# Sensor_Board.net
KiCad netlist of a schematic drawn in Altium Designer
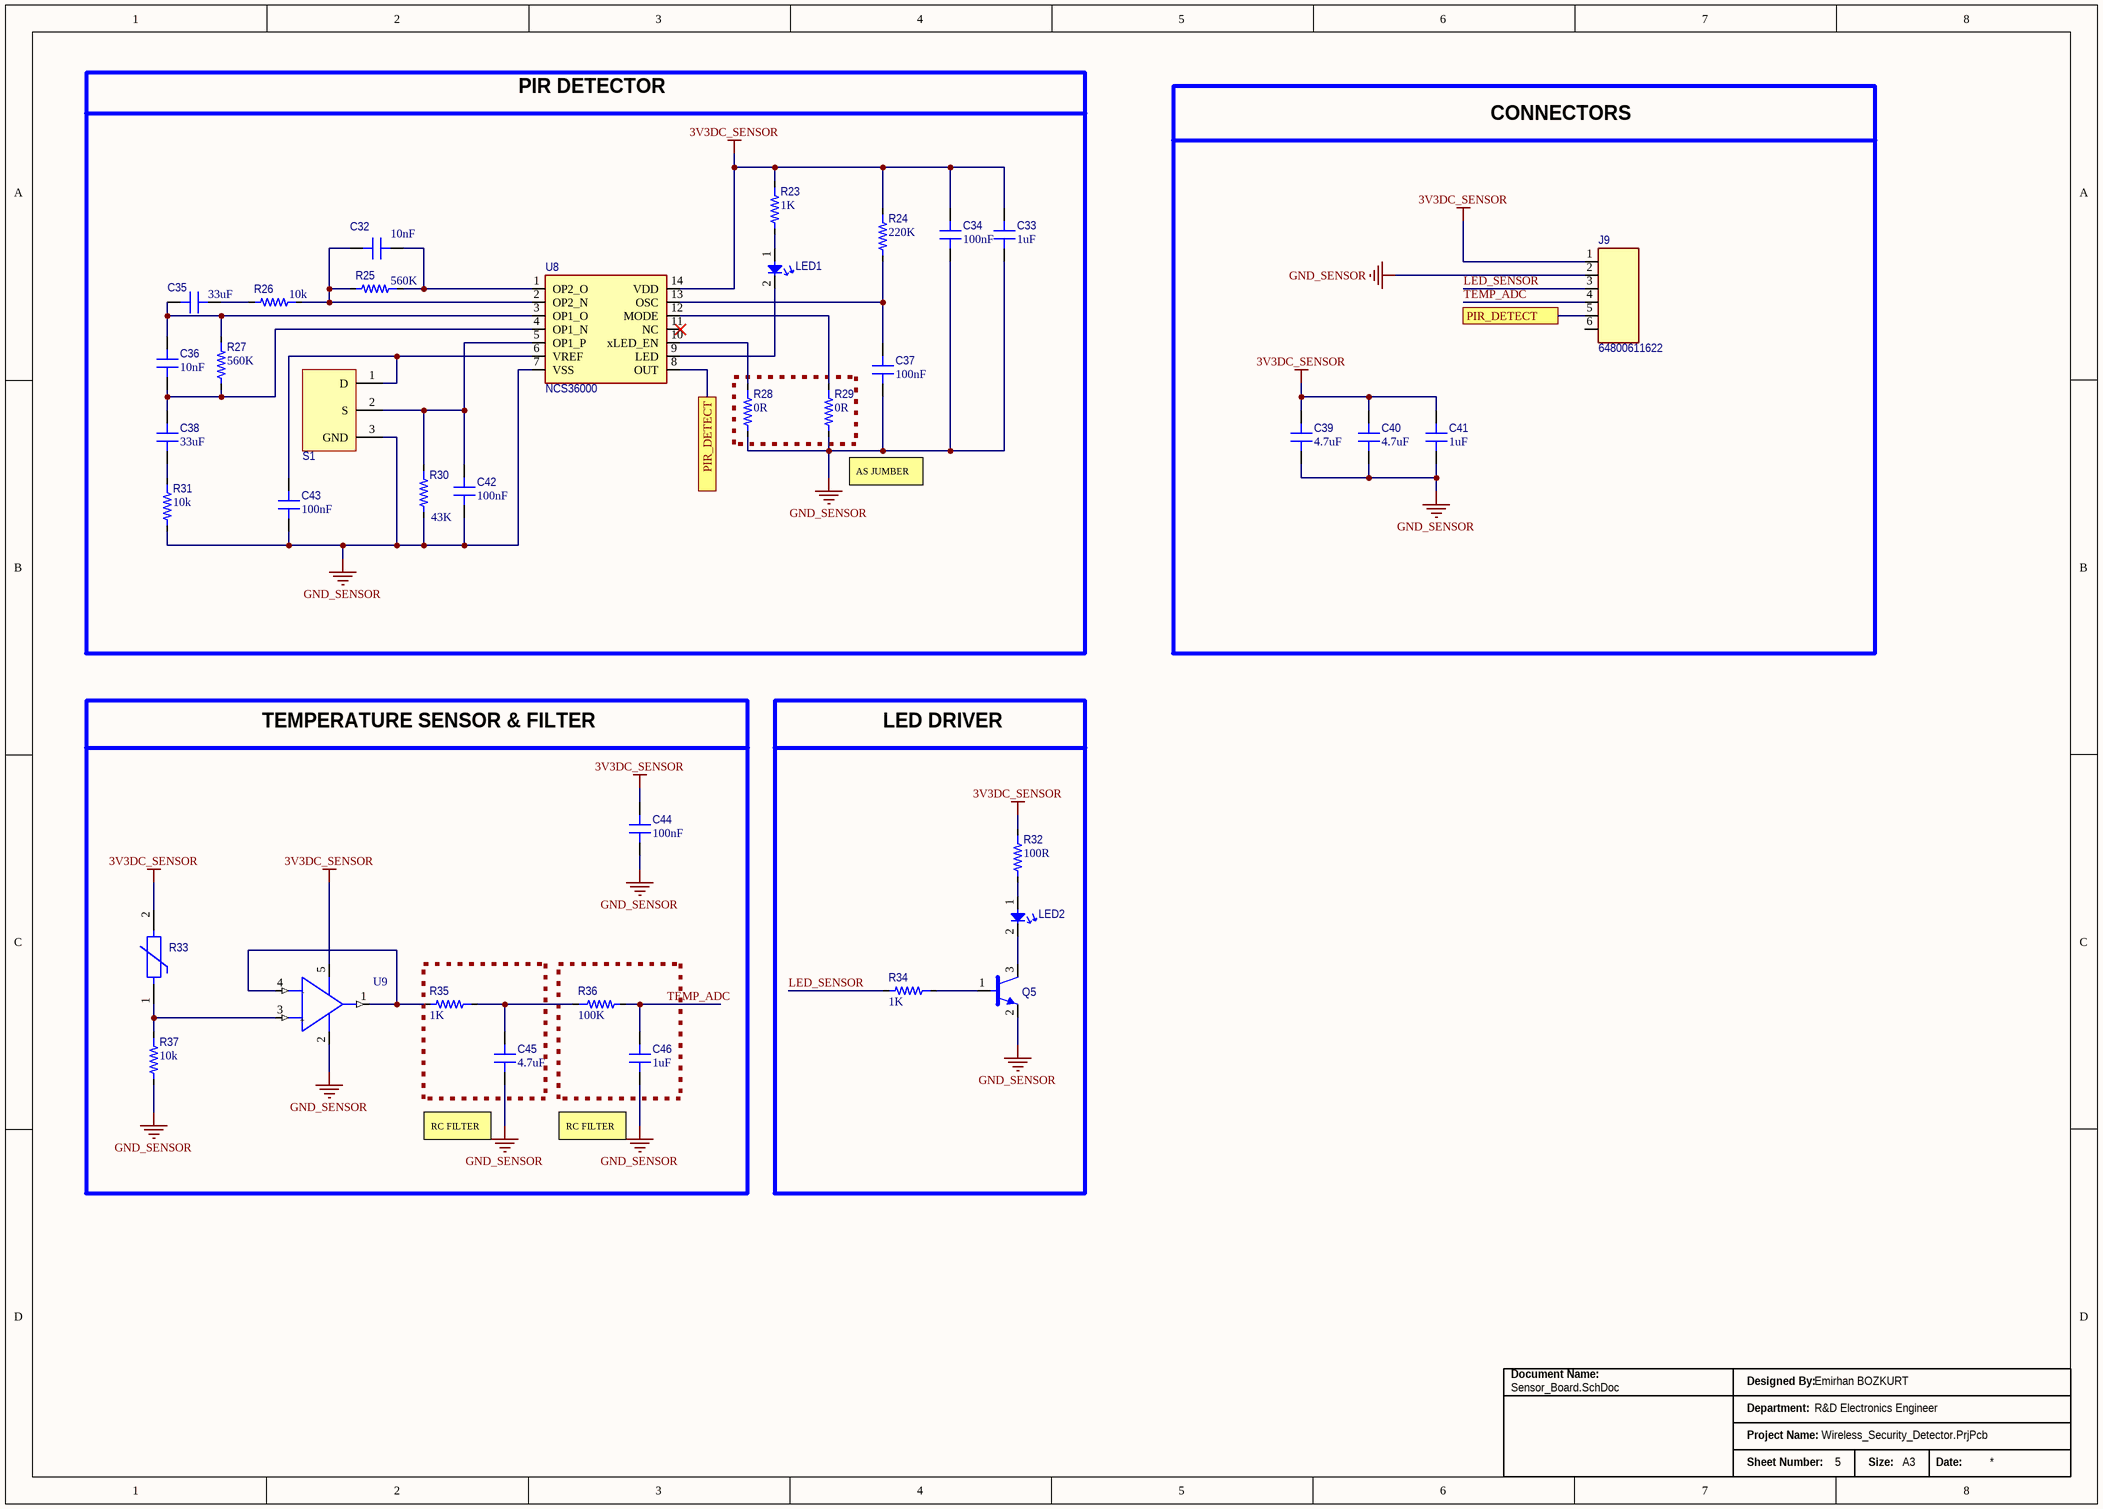
[diagram p0: Sensor_Board.SchDoc]

(export (version "E")
  (design (tool "Eeschema 10.0.6"))
  (components
    (comp (ref "C32")
      (value "10nF")
      (footprint "CAP_0603")
      (description "CAP CER 1000pF 50V X7R 0603")
      (fields
        (field (name "MANUFACTURER") "Samsung Electro-Mechanics")
        (field (name "Comment") "CL10B102KB8NNNC")
        (field (name "DESIGNED BY") "Emirhan Bozkurt")
      )
      (libsource (lib "Emirhan's") (part "CAP CER 10nF 0603"))
    )
    (comp (ref "C33")
      (value "1uF")
      (footprint "CAP_0805")
      (description "CAP CER 1uF 25V X5R 0805")
      (fields
        (field (name "MANUFACTURER") "Samsung Electro-Mechanics")
        (field (name "Comment") "CL21B105KBFNNNE")
        (field (name "DESIGNED BY") "Emirhan Bozkurt")
      )
      (libsource (lib "Emirhan's") (part "CAP CER 1uF 0805"))
    )
    (comp (ref "C34")
      (value "100nF")
      (footprint "CAP_0805")
      (description "CAP CER 0.1uF 50V X7R 0805")
      (fields (field (name "Comment") "1276-1003-2-ND") (field (name "DESIGNED BY") "Emirhan Bozkurt"))
      (libsource (lib "Emirhan's") (part "CAP CER 100nF 0805"))
    )
    (comp (ref "C35")
      (value "33uF")
      (footprint "CAP_0603")
      (description "CAP CER 33UF 6.3V X7S 1206")
      (fields
        (field (name "MANUFACTURER") "TDK Corporation")
        (field (name "Comment") "C3216X7S0J336M160AC")
        (field (name "DESIGNED BY") "Emirhan Bozkurt")
      )
      (libsource (lib "Emirhan's") (part "CAP CER 33uF 1206"))
    )
    (comp (ref "C36")
      (value "10nF")
      (footprint "CAP_0603")
      (description "CAP CER 1000pF 50V X7R 0603")
      (fields
        (field (name "MANUFACTURER") "Samsung Electro-Mechanics")
        (field (name "Comment") "CL10B102KB8NNNC")
        (field (name "DESIGNED BY") "Emirhan Bozkurt")
      )
      (libsource (lib "Emirhan's") (part "CAP CER 10nF 0603"))
    )
    (comp (ref "C37")
      (value "100nF")
      (footprint "CAP_0805")
      (description "CAP CER 0.1uF 50V X7R 0805")
      (fields (field (name "Comment") "1276-1003-2-ND") (field (name "DESIGNED BY") "Emirhan Bozkurt"))
      (libsource (lib "Emirhan's") (part "CAP CER 100nF 0805"))
    )
    (comp (ref "C38")
      (value "33uF")
      (footprint "CAP_0603")
      (description "CAP CER 33UF 6.3V X7S 1206")
      (fields
        (field (name "MANUFACTURER") "TDK Corporation")
        (field (name "Comment") "C3216X7S0J336M160AC")
        (field (name "DESIGNED BY") "Emirhan Bozkurt")
      )
      (libsource (lib "Emirhan's") (part "CAP CER 33uF 1206"))
    )
    (comp (ref "C39")
      (value "4.7uF")
      (footprint "CAP_0805")
      (description "CAP CER 4.7uF 25V X5R 0805")
      (fields
        (field (name "MANUFACTURER") "Samsung Electro-Mechanics")
        (field (name "Comment") "CL21A475KAQNNNE")
        (field (name "DESIGNED BY") "Emirhan Bozkurt")
      )
      (libsource (lib "Emirhan's") (part "CAP CER 4.7uF 0805"))
    )
    (comp (ref "C40")
      (value "4.7uF")
      (footprint "CAP_0805")
      (description "CAP CER 4.7uF 25V X5R 0805")
      (fields
        (field (name "MANUFACTURER") "Samsung Electro-Mechanics")
        (field (name "Comment") "CL21A475KAQNNNE")
        (field (name "DESIGNED BY") "Emirhan Bozkurt")
      )
      (libsource (lib "Emirhan's") (part "CAP CER 4.7uF 0805"))
    )
    (comp (ref "C41")
      (value "1uF")
      (footprint "CAP_0805")
      (description "CAP CER 1uF 25V X5R 0805")
      (fields
        (field (name "MANUFACTURER") "Samsung Electro-Mechanics")
        (field (name "Comment") "CL21B105KBFNNNE")
        (field (name "DESIGNED BY") "Emirhan Bozkurt")
      )
      (libsource (lib "Emirhan's") (part "CAP CER 1uF 0805"))
    )
    (comp (ref "C42")
      (value "100nF")
      (footprint "CAP_0805")
      (description "CAP CER 0.1uF 50V X7R 0805")
      (fields (field (name "Comment") "1276-1003-2-ND") (field (name "DESIGNED BY") "Emirhan Bozkurt"))
      (libsource (lib "Emirhan's") (part "CAP CER 100nF 0805"))
    )
    (comp (ref "C43")
      (value "100nF")
      (footprint "CAP_0805")
      (description "CAP CER 0.1uF 50V X7R 0805")
      (fields (field (name "Comment") "1276-1003-2-ND") (field (name "DESIGNED BY") "Emirhan Bozkurt"))
      (libsource (lib "Emirhan's") (part "CAP CER 100nF 0805"))
    )
    (comp (ref "C44")
      (value "100nF")
      (footprint "CAP_0805")
      (description "CAP CER 0.1uF 50V X7R 0805")
      (fields (field (name "Comment") "1276-1003-2-ND") (field (name "DESIGNED BY") "Emirhan Bozkurt"))
      (libsource (lib "Emirhan's") (part "CAP CER 100nF 0805"))
    )
    (comp (ref "C45")
      (value "4.7uF")
      (footprint "CAP_0805")
      (description "CAP CER 4.7uF 25V X5R 0805")
      (fields
        (field (name "MANUFACTURER") "Samsung Electro-Mechanics")
        (field (name "Comment") "CL21A475KAQNNNE")
        (field (name "DESIGNED BY") "Emirhan Bozkurt")
      )
      (libsource (lib "Emirhan's") (part "CAP CER 4.7uF 0805"))
    )
    (comp (ref "C46")
      (value "1uF")
      (footprint "CAP_0805")
      (description "CAP CER 1uF 25V X5R 0805")
      (fields
        (field (name "MANUFACTURER") "Samsung Electro-Mechanics")
        (field (name "Comment") "CL21B105KBFNNNE")
        (field (name "DESIGNED BY") "Emirhan Bozkurt")
      )
      (libsource (lib "Emirhan's") (part "CAP CER 1uF 0805"))
    )
    (comp (ref "J9")
      (value "64800611622")
      (footprint "64800611622")
      (description "WR-WTB WIRE-TO-BOARD CONNECTORS")
      (fields (field (name "MANUFACTURER") "WE") (field (name "DESIGNED BY") "Emirhan Bozkurt"))
      (libsource (lib "Emirhan's") (part "64800611622-CONN-6P"))
    )
    (comp (ref "LED1")
      (value "LTST-C171GKT")
      (footprint "LED GREEN 0805")
      (description "LED GREEN CLEAR SMD")
      (fields (field (name "MANUFACTURER") "Lite-On Inc.") (field (name "DESIGNED BY") "Emirhan Bozkurt"))
      (libsource (lib "Emirhan's") (part "LED GREEN"))
    )
    (comp (ref "LED2")
      (value "LTST-C171KRKT")
      (footprint "LED RED 0805")
      (description "LED RED CLEAR SMD")
      (fields (field (name "MANUFACTURER") "Lite-On Inc.") (field (name "DESIGNED BY") "Emirhan Bozkurt"))
      (libsource (lib "Emirhan's") (part "LED RED"))
    )
    (comp (ref "Q5")
      (value "MMBT3904-7-F")
      (footprint "SOT-23F")
      (description "TRANS NPN 40V 0.2A SOT-23-3")
      (libsource (lib "Emirhan's") (part "MMBT3904-7-F"))
    )
    (comp (ref "R23")
      (value "1K")
      (footprint "RES_0603")
      (description "RES 1K 1% 1/10W 0603")
      (fields
        (field (name "SUPPIER PART NUMBER") "311-1.00KHRCT-ND")
        (field (name "MANUFACTURER") "YAGEO")
        (field (name "DESIGNED BY") "Emirhan Bozkurt")
      )
      (libsource (lib "Emirhan's") (part "RES 1K 0603"))
    )
    (comp (ref "R24")
      (value "220K")
      (footprint "RES_0603")
      (description "RES 220K OHM 1% 1/10W 0603")
      (fields
        (field (name "SUPPIER PART NUMBER") "311-220KHRTR-ND")
        (field (name "MANUFACTURER") "YAGEO")
        (field (name "DESIGNED BY") "Emirhan Bozkurt")
      )
      (libsource (lib "Emirhan's") (part "RES 220K 0603"))
    )
    (comp (ref "R25")
      (value "560K")
      (footprint "RES_0603")
      (description "RES 1560K 1% 1/10W 0603")
      (fields
        (field (name "SUPPIER PART NUMBER") "311-560KHRCT-ND")
        (field (name "MANUFACTURER") "YAGEO")
        (field (name "DESIGNED BY") "Emirhan Bozkurt")
      )
      (libsource (lib "Emirhan's") (part "RES 560K 0603"))
    )
    (comp (ref "R26")
      (value "10k")
      (footprint "RES_0603")
      (description "RES 10K OHM 1% 1/10W 0603")
      (fields
        (field (name "SUPPIER PART NUMBER") "311-10.0KHRTR-ND")
        (field (name "MANUFACTURER") "YAGEO")
        (field (name "DESIGNED BY") "Emirhan Bozkurt")
      )
      (libsource (lib "Emirhan's") (part "RES 10K 0603"))
    )
    (comp (ref "R27")
      (value "560K")
      (footprint "RES_0603")
      (description "RES 1560K 1% 1/10W 0603")
      (fields
        (field (name "SUPPIER PART NUMBER") "311-560KHRCT-ND")
        (field (name "MANUFACTURER") "YAGEO")
        (field (name "DESIGNED BY") "Emirhan Bozkurt")
      )
      (libsource (lib "Emirhan's") (part "RES 560K 0603"))
    )
    (comp (ref "R28")
      (value "0R")
      (footprint "RES_0603")
      (description "RES 0 OHM 1% 1/10W 0603")
      (fields
        (field (name "SUPPIER PART NUMBER") "2997-CR160000FTR-ND")
        (field (name "MANUFACTURER") "YAGEO")
        (field (name "DESIGNED BY") "Emirhan Bozkurt")
      )
      (libsource (lib "Emirhan's") (part "RES 0R 0603"))
    )
    (comp (ref "R29")
      (value "0R")
      (footprint "RES_0603")
      (description "RES 0 OHM 1% 1/10W 0603")
      (fields
        (field (name "SUPPIER PART NUMBER") "2997-CR160000FTR-ND")
        (field (name "MANUFACTURER") "YAGEO")
        (field (name "DESIGNED BY") "Emirhan Bozkurt")
      )
      (libsource (lib "Emirhan's") (part "RES 0R 0603"))
    )
    (comp (ref "R30")
      (value "43K")
      (footprint "RES_0603")
      (description "RES 43K OHM 1% 1/10W 0603")
      (fields
        (field (name "SUPPIER PART NUMBER") "311-43.0KHRTR-ND")
        (field (name "MANUFACTURER") "YAGEO")
        (field (name "DESIGNED BY") "Emirhan Bozkurt")
      )
      (libsource (lib "Emirhan's") (part "RES 43K 0603"))
    )
    (comp (ref "R31")
      (value "10k")
      (footprint "RES_0603")
      (description "RES 10K OHM 1% 1/10W 0603")
      (fields
        (field (name "SUPPIER PART NUMBER") "311-10.0KHRTR-ND")
        (field (name "MANUFACTURER") "YAGEO")
        (field (name "DESIGNED BY") "Emirhan Bozkurt")
      )
      (libsource (lib "Emirhan's") (part "RES 10K 0603"))
    )
    (comp (ref "R32")
      (value "100R")
      (footprint "RES_0603")
      (description "RES 100 OHM 1% 1/10W 0603")
      (fields
        (field (name "SUPPIER PART NUMBER") "311-100HRTR-ND")
        (field (name "MANUFACTURER") "YAGEO")
        (field (name "DESIGNED BY") "Emirhan Bozkurt")
      )
      (libsource (lib "Emirhan's") (part "RES 100R 0603"))
    )
    (comp (ref "R33")
      (value "TFPT1206L1002FM")
      (footprint "PTC_1206")
      (description "SENSOR PTC 10KOHM 1% 1206")
      (fields (field (name "DESIGNED BY") "Emirhan Bozkurt"))
      (libsource (lib "Emirhan's") (part "TFPT1206L1002FM"))
    )
    (comp (ref "R34")
      (value "1K")
      (footprint "RES_0603")
      (description "RES 1K 1% 1/10W 0603")
      (fields
        (field (name "SUPPIER PART NUMBER") "311-1.00KHRCT-ND")
        (field (name "MANUFACTURER") "YAGEO")
        (field (name "DESIGNED BY") "Emirhan Bozkurt")
      )
      (libsource (lib "Emirhan's") (part "RES 1K 0603"))
    )
    (comp (ref "R35")
      (value "1K")
      (footprint "RES_0603")
      (description "RES 1K 1% 1/10W 0603")
      (fields
        (field (name "SUPPIER PART NUMBER") "311-1.00KHRCT-ND")
        (field (name "MANUFACTURER") "YAGEO")
        (field (name "DESIGNED BY") "Emirhan Bozkurt")
      )
      (libsource (lib "Emirhan's") (part "RES 1K 0603"))
    )
    (comp (ref "R36")
      (value "100K")
      (footprint "RES_0603")
      (description "RES 100K OHM 1% 1/10W 0603")
      (fields
        (field (name "SUPPIER PART NUMBER") "311-100KHRCT-ND")
        (field (name "MANUFACTURER") "YAGEO")
        (field (name "DESIGNED BY") "Emirhan Bozkurt")
      )
      (libsource (lib "Emirhan's") (part "RES 100K 0603"))
    )
    (comp (ref "R37")
      (value "10k")
      (footprint "RES_0603")
      (description "RES 10K OHM 1% 1/10W 0603")
      (fields
        (field (name "SUPPIER PART NUMBER") "311-10.0KHRTR-ND")
        (field (name "MANUFACTURER") "YAGEO")
        (field (name "DESIGNED BY") "Emirhan Bozkurt")
      )
      (libsource (lib "Emirhan's") (part "RES 10K 0603"))
    )
    (comp (ref "S1")
      (value "LHI 878/3902")
      (footprint "LHI 878")
      (description "SENSOR PYRO DETECTOR DUAL MOTION")
      (fields (field (name "DESIGNED BY") "Emirhan Bozkurt"))
      (libsource (lib "Emirhan's") (part "LHI 878/3902"))
    )
    (comp (ref "U8")
      (value "NCS36000")
      (footprint "NCS36000")
      (description "IC PIR DETECTOR CTLR 14SOIC")
      (fields (field (name "MANUFACTURER") "Onsemi") (field (name "DESIGNED BY") "Emirhan Bozkurt"))
      (libsource (lib "Emirhan's") (part "NCS36000"))
    )
    (comp (ref "U9")
      (value "OPA314AIDBVR")
      (footprint "OPA314")
      (description "IC OPAMP GP 1 CIRCUIT SOT23-5")
      (fields
        (field (name "MANUFACTURER") "Texas Instruments")
        (field (name "DESIGNED BY") "Emirhan Bozkurt")
      )
      (libsource (lib "Wireless_Security_Detector") (part "OPA314AIDBVR"))
    )
  )
  (nets
    (net (code "1") (name "/LED_SENSOR") (class "Default")
      (node (ref "J9") (pin "3") (pintype "passive"))
      (node (ref "R34") (pin "1") (pinfunction "1_1") (pintype "passive"))
    )
    (net (code "2") (name "/PIR_DETECT") (class "Default")
      (node (ref "J9") (pin "5") (pintype "passive"))
      (node (ref "U8") (pin "8") (pinfunction "OUT_8") (pintype "passive"))
    )
    (net (code "3") (name "/TEMP_ADC") (class "Default")
      (node (ref "C46") (pin "2") (pinfunction "2_2") (pintype "passive"))
      (node (ref "J9") (pin "4") (pintype "passive"))
      (node (ref "R36") (pin "1") (pinfunction "1_1") (pintype "passive"))
    )
    (net (code "4") (name "3V3DC_SENSOR") (class "Default")
      (node (ref "C33") (pin "2") (pinfunction "2_2") (pintype "passive"))
      (node (ref "C34") (pin "2") (pinfunction "2_2") (pintype "passive"))
      (node (ref "C39") (pin "2") (pinfunction "2_2") (pintype "passive"))
      (node (ref "C40") (pin "2") (pinfunction "2_2") (pintype "passive"))
      (node (ref "C41") (pin "2") (pinfunction "2_2") (pintype "passive"))
      (node (ref "C44") (pin "2") (pinfunction "2_2") (pintype "passive"))
      (node (ref "J9") (pin "1") (pintype "passive"))
      (node (ref "R23") (pin "2") (pinfunction "2_2") (pintype "passive"))
      (node (ref "R24") (pin "2") (pinfunction "2_2") (pintype "passive"))
      (node (ref "R32") (pin "2") (pinfunction "2_2") (pintype "passive"))
      (node (ref "R33") (pin "2") (pinfunction "2_2") (pintype "passive"))
      (node (ref "U8") (pin "14") (pinfunction "VDD_14") (pintype "passive"))
      (node (ref "U9") (pin "5") (pinfunction "V-_5") (pintype "power_in"))
    )
    (net (code "5") (name "GND_SENSOR") (class "Default")
      (node (ref "C33") (pin "1") (pinfunction "1_1") (pintype "passive"))
      (node (ref "C34") (pin "1") (pinfunction "1_1") (pintype "passive"))
      (node (ref "C37") (pin "1") (pinfunction "1_1") (pintype "passive"))
      (node (ref "C39") (pin "1") (pinfunction "1_1") (pintype "passive"))
      (node (ref "C40") (pin "1") (pinfunction "1_1") (pintype "passive"))
      (node (ref "C41") (pin "1") (pinfunction "1_1") (pintype "passive"))
      (node (ref "C42") (pin "1") (pinfunction "1_1") (pintype "passive"))
      (node (ref "C43") (pin "1") (pinfunction "1_1") (pintype "passive"))
      (node (ref "C44") (pin "1") (pinfunction "1_1") (pintype "passive"))
      (node (ref "C45") (pin "1") (pinfunction "1_1") (pintype "passive"))
      (node (ref "C46") (pin "1") (pinfunction "1_1") (pintype "passive"))
      (node (ref "J9") (pin "2") (pintype "passive"))
      (node (ref "Q5") (pin "2") (pinfunction "E_2") (pintype "passive"))
      (node (ref "R28") (pin "1") (pinfunction "1_1") (pintype "passive"))
      (node (ref "R29") (pin "1") (pinfunction "1_1") (pintype "passive"))
      (node (ref "R30") (pin "1") (pinfunction "1_1") (pintype "passive"))
      (node (ref "R31") (pin "1") (pinfunction "1_1") (pintype "passive"))
      (node (ref "R37") (pin "1") (pinfunction "1_1") (pintype "passive"))
      (node (ref "S1") (pin "3") (pinfunction "GND_3") (pintype "passive"))
      (node (ref "U8") (pin "7") (pinfunction "VSS_7") (pintype "passive"))
      (node (ref "U9") (pin "2") (pinfunction "V+_2") (pintype "power_in"))
    )
    (net (code "6") (name "Net-(C35-Pad2)") (class "Default")
      (node (ref "C35") (pin "2") (pinfunction "2_2") (pintype "passive"))
      (node (ref "R26") (pin "1") (pinfunction "1_1") (pintype "passive"))
    )
    (net (code "7") (name "Net-(C38-Pad1)") (class "Default")
      (node (ref "C38") (pin "1") (pinfunction "1_1") (pintype "passive"))
      (node (ref "R31") (pin "2") (pinfunction "2_2") (pintype "passive"))
    )
    (net (code "8") (name "Net-(C45-Pad2)") (class "Default")
      (node (ref "C45") (pin "2") (pinfunction "2_2") (pintype "passive"))
      (node (ref "R35") (pin "2") (pinfunction "2_2") (pintype "passive"))
      (node (ref "R36") (pin "2") (pinfunction "2_2") (pintype "passive"))
    )
    (net (code "9") (name "Net-(LED1-Pad1)") (class "Default")
      (node (ref "LED1") (pin "1") (pinfunction "1_1") (pintype "passive"))
      (node (ref "R23") (pin "1") (pinfunction "1_1") (pintype "passive"))
    )
    (net (code "10") (name "Net-(LED2-Pad1)") (class "Default")
      (node (ref "LED2") (pin "1") (pinfunction "1_1") (pintype "passive"))
      (node (ref "R32") (pin "1") (pinfunction "1_1") (pintype "passive"))
    )
    (net (code "11") (name "Net-(Q5-B)") (class "Default")
      (node (ref "Q5") (pin "1") (pinfunction "B_1") (pintype "passive"))
      (node (ref "R34") (pin "2") (pinfunction "2_2") (pintype "passive"))
    )
    (net (code "12") (name "Net-(Q5-C)") (class "Default")
      (node (ref "LED2") (pin "2") (pinfunction "2_2") (pintype "passive"))
      (node (ref "Q5") (pin "3") (pinfunction "C_3") (pintype "passive"))
    )
    (net (code "13") (name "Net-(S1-D)") (class "Default")
      (node (ref "C43") (pin "2") (pinfunction "2_2") (pintype "passive"))
      (node (ref "S1") (pin "1") (pinfunction "D_1") (pintype "passive"))
      (node (ref "U8") (pin "6") (pinfunction "VREF_6") (pintype "passive"))
    )
    (net (code "14") (name "Net-(S1-S)") (class "Default")
      (node (ref "C42") (pin "2") (pinfunction "2_2") (pintype "passive"))
      (node (ref "R30") (pin "2") (pinfunction "2_2") (pintype "passive"))
      (node (ref "S1") (pin "2") (pinfunction "S_2") (pintype "passive"))
      (node (ref "U8") (pin "5") (pinfunction "OP1_P_5") (pintype "passive"))
    )
    (net (code "15") (name "Net-(U8-LED)") (class "Default")
      (node (ref "LED1") (pin "2") (pinfunction "2_2") (pintype "passive"))
      (node (ref "U8") (pin "9") (pinfunction "LED_9") (pintype "passive"))
    )
    (net (code "16") (name "Net-(U8-MODE)") (class "Default")
      (node (ref "R29") (pin "2") (pinfunction "2_2") (pintype "passive"))
      (node (ref "U8") (pin "12") (pinfunction "MODE_12") (pintype "passive"))
    )
    (net (code "17") (name "Net-(U8-OP1_N)") (class "Default")
      (node (ref "C36") (pin "1") (pinfunction "1_1") (pintype "passive"))
      (node (ref "C38") (pin "2") (pinfunction "2_2") (pintype "passive"))
      (node (ref "R27") (pin "1") (pinfunction "1_1") (pintype "passive"))
      (node (ref "U8") (pin "4") (pinfunction "OP1_N_4") (pintype "passive"))
    )
    (net (code "18") (name "Net-(U8-OP1_O)") (class "Default")
      (node (ref "C35") (pin "1") (pinfunction "1_1") (pintype "passive"))
      (node (ref "C36") (pin "2") (pinfunction "2_2") (pintype "passive"))
      (node (ref "R27") (pin "2") (pinfunction "2_2") (pintype "passive"))
      (node (ref "U8") (pin "3") (pinfunction "OP1_O_3") (pintype "passive"))
    )
    (net (code "19") (name "Net-(U8-OP2_N)") (class "Default")
      (node (ref "C32") (pin "1") (pinfunction "1_1") (pintype "passive"))
      (node (ref "R25") (pin "1") (pinfunction "1_1") (pintype "passive"))
      (node (ref "R26") (pin "2") (pinfunction "2_2") (pintype "passive"))
      (node (ref "U8") (pin "2") (pinfunction "OP2_N_2") (pintype "passive"))
    )
    (net (code "20") (name "Net-(U8-OP2_O)") (class "Default")
      (node (ref "C32") (pin "2") (pinfunction "2_2") (pintype "passive"))
      (node (ref "R25") (pin "2") (pinfunction "2_2") (pintype "passive"))
      (node (ref "U8") (pin "1") (pinfunction "OP2_O_1") (pintype "passive"))
    )
    (net (code "21") (name "Net-(U8-OSC)") (class "Default")
      (node (ref "C37") (pin "2") (pinfunction "2_2") (pintype "passive"))
      (node (ref "R24") (pin "1") (pinfunction "1_1") (pintype "passive"))
      (node (ref "U8") (pin "13") (pinfunction "OSC_13") (pintype "passive"))
    )
    (net (code "22") (name "Net-(U8-xLED_EN)") (class "Default")
      (node (ref "R28") (pin "2") (pinfunction "2_2") (pintype "passive"))
      (node (ref "U8") (pin "10") (pinfunction "xLED_EN_10") (pintype "passive"))
    )
    (net (code "23") (name "Net-(U9-+IN)") (class "Default")
      (node (ref "R33") (pin "1") (pinfunction "1_1") (pintype "passive"))
      (node (ref "R37") (pin "2") (pinfunction "2_2") (pintype "passive"))
      (node (ref "U9") (pin "3") (pinfunction "+IN_3") (pintype "input"))
    )
    (net (code "24") (name "Net-(U9--IN)") (class "Default")
      (node (ref "R35") (pin "1") (pinfunction "1_1") (pintype "passive"))
      (node (ref "U9") (pin "1") (pinfunction "OUT_1") (pintype "output"))
      (node (ref "U9") (pin "4") (pinfunction "-IN_4") (pintype "input"))
    )
    (net (code "25") (name "unconnected-(J9-Pad6)") (class "Default")
      (node (ref "J9") (pin "6") (pintype "passive"))
    )
    (net (code "26") (name "unconnected-(U8-NC-Pad11)") (class "Default")
      (node (ref "U8") (pin "11") (pinfunction "NC_11") (pintype "passive+no_connect"))
    )
  )
)
